# Sheet1.net
KiCad netlist of a schematic drawn in Altium Designer
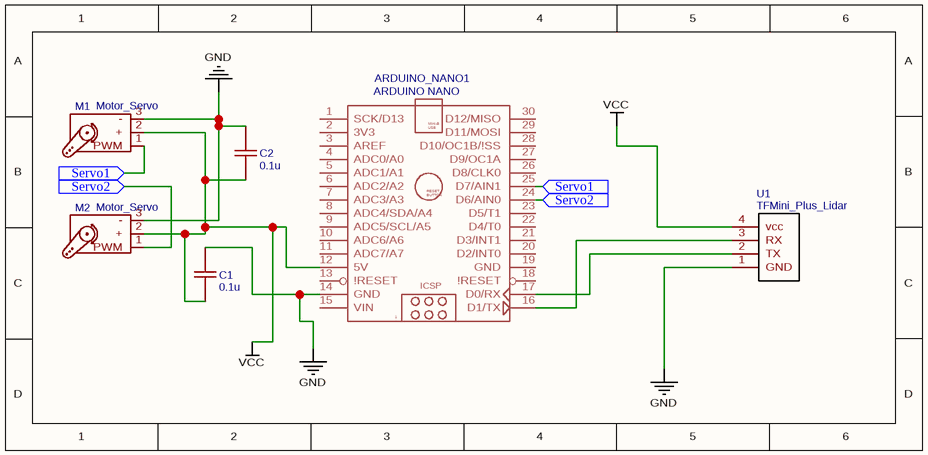
[diagram p0: Sheet1.schdoc]

(export (version "E")
  (design (tool "Eeschema 10.0.6"))
  (components
    (comp (ref "ARDUINO_NANO1")
      (value "ARDUINO NANO")
      (fields (field (name "CONTRIBUTOR") "dhya"))
      (libsource (lib "altium-import") (part "root_2_ARDUINO NANO_"))
    )
    (comp (ref "C1")
      (value "0.1u")
      (fields (field (name "CONTRIBUTOR") "LCEDA_Lib"))
      (libsource (lib "altium-import") (part "root_1_0.1u_"))
    )
    (comp (ref "C2")
      (value "0.1u")
      (fields (field (name "CONTRIBUTOR") "LCEDA_Lib"))
      (libsource (lib "altium-import") (part "root_1_0.1u_"))
    )
    (comp (ref "M1")
      (value "Motor_Servo")
      (fields (field (name "CONTRIBUTOR") "KiCAD"))
      (libsource (lib "altium-import") (part "root_2_Motor_Servo_"))
    )
    (comp (ref "M2")
      (value "Motor_Servo")
      (fields (field (name "CONTRIBUTOR") "KiCAD"))
      (libsource (lib "altium-import") (part "root_2_Motor_Servo_"))
    )
    (comp (ref "U1")
      (value "TFMini_Plus_Lidar")
      (fields (field (name "CONTRIBUTOR") "tiago.valadares"))
      (libsource (lib "altium-import") (part "root_0_TFMini_Plus_Lidar_"))
    )
  )
  (nets
    (net (code "1") (name "/Servo1") (class "Default")
      (node (ref "ARDUINO_NANO1") (pin "25") (pinfunction "D7/AIN1_25") (pintype "passive"))
      (node (ref "M1") (pin "1") (pinfunction "PWM_1") (pintype "passive"))
    )
    (net (code "2") (name "/Servo2") (class "Default")
      (node (ref "ARDUINO_NANO1") (pin "24") (pinfunction "D6/AIN0_24") (pintype "passive"))
      (node (ref "M2") (pin "1") (pinfunction "PWM_1") (pintype "passive"))
    )
    (net (code "3") (name "GND") (class "Default")
      (node (ref "ARDUINO_NANO1") (pin "14") (pinfunction "GND_14") (pintype "passive"))
      (node (ref "C1") (pin "2") (pinfunction "2_2") (pintype "passive"))
      (node (ref "C2") (pin "2") (pinfunction "2_2") (pintype "passive"))
      (node (ref "M1") (pin "3") (pinfunction "-_3") (pintype "passive"))
      (node (ref "M2") (pin "3") (pinfunction "-_3") (pintype "passive"))
      (node (ref "U1") (pin "1") (pinfunction "GND_1") (pintype "passive"))
    )
    (net (code "4") (name "Net-(ARDUINO_NANO1-D0{slash}RX)") (class "Default")
      (node (ref "ARDUINO_NANO1") (pin "17") (pinfunction "D0/RX_17") (pintype "passive"))
      (node (ref "U1") (pin "2") (pinfunction "TX_2") (pintype "passive"))
    )
    (net (code "5") (name "Net-(ARDUINO_NANO1-D1{slash}TX)") (class "Default")
      (node (ref "ARDUINO_NANO1") (pin "16") (pinfunction "D1/TX_16") (pintype "passive"))
      (node (ref "U1") (pin "3") (pinfunction "RX_3") (pintype "passive"))
    )
    (net (code "6") (name "VCC") (class "Default")
      (node (ref "ARDUINO_NANO1") (pin "12") (pinfunction "5V_12") (pintype "passive"))
      (node (ref "C1") (pin "1") (pinfunction "1_1") (pintype "passive"))
      (node (ref "C2") (pin "1") (pinfunction "1_1") (pintype "passive"))
      (node (ref "M1") (pin "2") (pinfunction "+_2") (pintype "passive"))
      (node (ref "M2") (pin "2") (pinfunction "+_2") (pintype "passive"))
      (node (ref "U1") (pin "4") (pinfunction "vcc_4") (pintype "passive"))
    )
    (net (code "7") (name "unconnected-(ARDUINO_NANO1-!RESET-Pad13)") (class "Default")
      (node (ref "ARDUINO_NANO1") (pin "13") (pinfunction "!RESET_13") (pintype "passive"))
    )
    (net (code "8") (name "unconnected-(ARDUINO_NANO1-!RESET-Pad18)") (class "Default")
      (node (ref "ARDUINO_NANO1") (pin "18") (pinfunction "!RESET_18") (pintype "passive"))
    )
    (net (code "9") (name "unconnected-(ARDUINO_NANO1-3V3-Pad2)") (class "Default")
      (node (ref "ARDUINO_NANO1") (pin "2") (pinfunction "3V3_2") (pintype "passive"))
    )
    (net (code "10") (name "unconnected-(ARDUINO_NANO1-ADC0{slash}A0-Pad4)") (class "Default")
      (node (ref "ARDUINO_NANO1") (pin "4") (pinfunction "ADC0/A0_4") (pintype "passive"))
    )
    (net (code "11") (name "unconnected-(ARDUINO_NANO1-ADC1{slash}A1-Pad5)") (class "Default")
      (node (ref "ARDUINO_NANO1") (pin "5") (pinfunction "ADC1/A1_5") (pintype "passive"))
    )
    (net (code "12") (name "unconnected-(ARDUINO_NANO1-ADC2{slash}A2-Pad6)") (class "Default")
      (node (ref "ARDUINO_NANO1") (pin "6") (pinfunction "ADC2/A2_6") (pintype "passive"))
    )
    (net (code "13") (name "unconnected-(ARDUINO_NANO1-ADC3{slash}A3-Pad7)") (class "Default")
      (node (ref "ARDUINO_NANO1") (pin "7") (pinfunction "ADC3/A3_7") (pintype "passive"))
    )
    (net (code "14") (name "unconnected-(ARDUINO_NANO1-ADC4{slash}SDA{slash}A4-Pad8)") (class "Default")
      (node (ref "ARDUINO_NANO1") (pin "8") (pinfunction "ADC4/SDA/A4_8") (pintype "passive"))
    )
    (net (code "15") (name "unconnected-(ARDUINO_NANO1-ADC5{slash}SCL{slash}A5-Pad9)") (class "Default")
      (node (ref "ARDUINO_NANO1") (pin "9") (pinfunction "ADC5/SCL/A5_9") (pintype "passive"))
    )
    (net (code "16") (name "unconnected-(ARDUINO_NANO1-ADC6{slash}A6-Pad10)") (class "Default")
      (node (ref "ARDUINO_NANO1") (pin "10") (pinfunction "ADC6/A6_10") (pintype "passive"))
    )
    (net (code "17") (name "unconnected-(ARDUINO_NANO1-ADC7{slash}A7-Pad11)") (class "Default")
      (node (ref "ARDUINO_NANO1") (pin "11") (pinfunction "ADC7/A7_11") (pintype "passive"))
    )
    (net (code "18") (name "unconnected-(ARDUINO_NANO1-AREF-Pad3)") (class "Default")
      (node (ref "ARDUINO_NANO1") (pin "3") (pinfunction "AREF_3") (pintype "passive"))
    )
    (net (code "19") (name "unconnected-(ARDUINO_NANO1-D2{slash}INT0-Pad20)") (class "Default")
      (node (ref "ARDUINO_NANO1") (pin "20") (pinfunction "D2/INT0_20") (pintype "passive"))
    )
    (net (code "20") (name "unconnected-(ARDUINO_NANO1-D3{slash}INT1-Pad21)") (class "Default")
      (node (ref "ARDUINO_NANO1") (pin "21") (pinfunction "D3/INT1_21") (pintype "passive"))
    )
    (net (code "21") (name "unconnected-(ARDUINO_NANO1-D4{slash}T0-Pad22)") (class "Default")
      (node (ref "ARDUINO_NANO1") (pin "22") (pinfunction "D4/T0_22") (pintype "passive"))
    )
    (net (code "22") (name "unconnected-(ARDUINO_NANO1-D5{slash}T1-Pad23)") (class "Default")
      (node (ref "ARDUINO_NANO1") (pin "23") (pinfunction "D5/T1_23") (pintype "passive"))
    )
    (net (code "23") (name "unconnected-(ARDUINO_NANO1-D8{slash}CLK0-Pad26)") (class "Default")
      (node (ref "ARDUINO_NANO1") (pin "26") (pinfunction "D8/CLK0_26") (pintype "passive"))
    )
    (net (code "24") (name "unconnected-(ARDUINO_NANO1-D9{slash}OC1A-Pad27)") (class "Default")
      (node (ref "ARDUINO_NANO1") (pin "27") (pinfunction "D9/OC1A_27") (pintype "passive"))
    )
    (net (code "25") (name "unconnected-(ARDUINO_NANO1-D10{slash}OC1B{slash}!SS-Pad28)") (class "Default")
      (node (ref "ARDUINO_NANO1") (pin "28") (pinfunction "D10/OC1B/!SS_28") (pintype "passive"))
    )
    (net (code "26") (name "unconnected-(ARDUINO_NANO1-D11{slash}MOSI-Pad29)") (class "Default")
      (node (ref "ARDUINO_NANO1") (pin "29") (pinfunction "D11/MOSI_29") (pintype "passive"))
    )
    (net (code "27") (name "unconnected-(ARDUINO_NANO1-D12{slash}MISO-Pad30)") (class "Default")
      (node (ref "ARDUINO_NANO1") (pin "30") (pinfunction "D12/MISO_30") (pintype "passive"))
    )
    (net (code "28") (name "unconnected-(ARDUINO_NANO1-GND-Pad19)") (class "Default")
      (node (ref "ARDUINO_NANO1") (pin "19") (pinfunction "GND_19") (pintype "passive"))
    )
    (net (code "29") (name "unconnected-(ARDUINO_NANO1-SCK{slash}D13-Pad1)") (class "Default")
      (node (ref "ARDUINO_NANO1") (pin "1") (pinfunction "SCK/D13_1") (pintype "passive"))
    )
    (net (code "30") (name "unconnected-(ARDUINO_NANO1-VIN-Pad15)") (class "Default")
      (node (ref "ARDUINO_NANO1") (pin "15") (pinfunction "VIN_15") (pintype "passive"))
    )
  )
)
